# Power_Distribution_-_Spares_6-9.net
KiCad netlist of a schematic drawn in Altium Designer
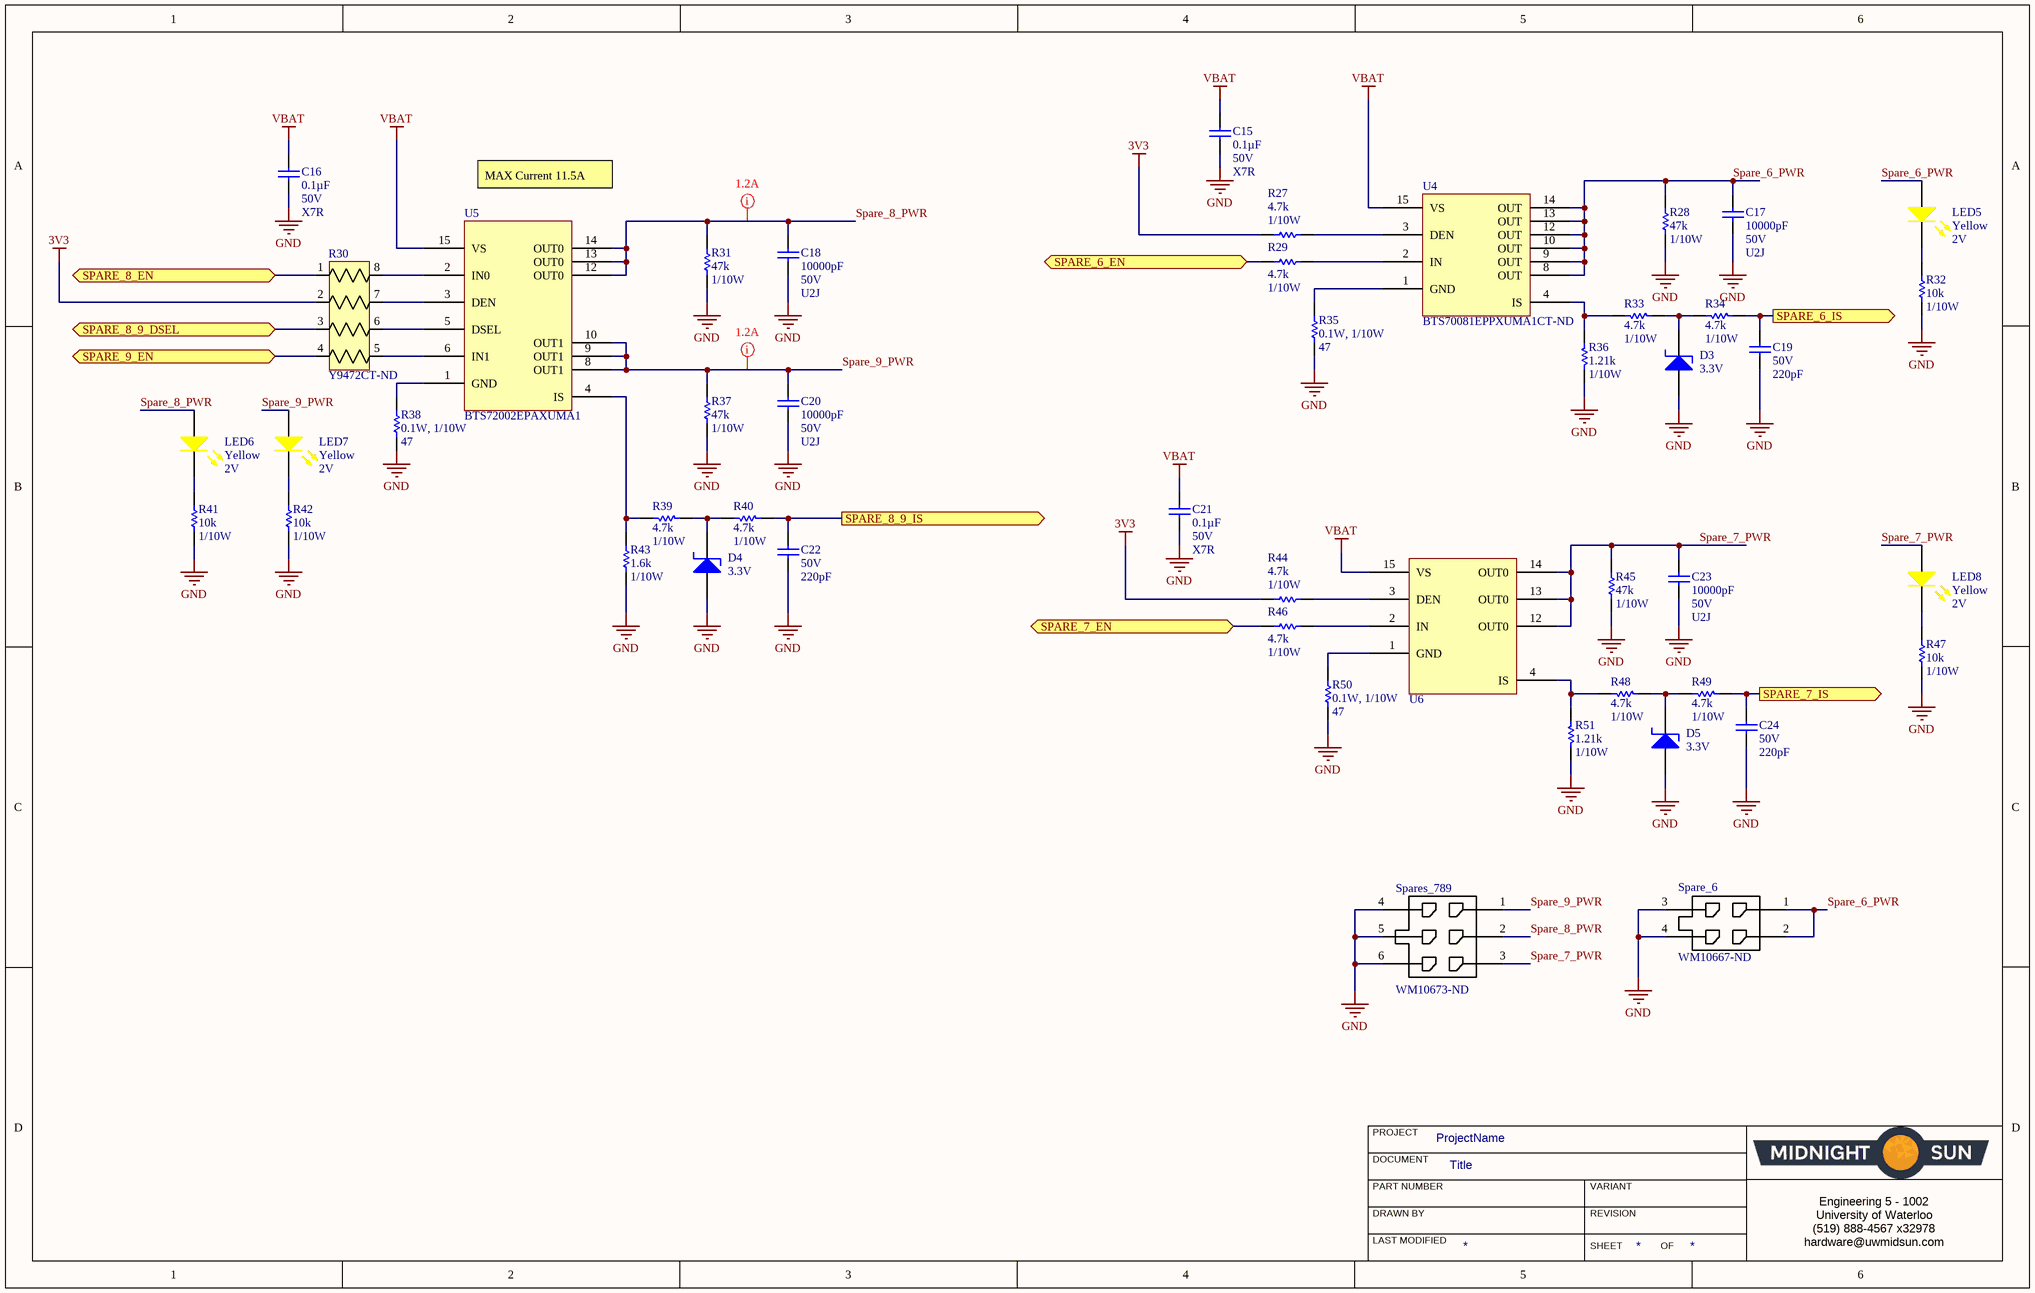
[diagram p0: Power Distribution - Spares 6-9.SchDoc]

(export (version "E")
  (design (tool "Eeschema 10.0.6"))
  (components
    (comp (ref "C15")
      (value "CAP CER 0.1UF 50V 10% X7R 0603")
      (footprint "CAP, 0603")
      (description "0.10µF ±10% 50V Ceramic Capacitor X7R 0603 (1608 Metric)")
      (fields
        (field (name "TOLERANCE") "±10%")
        (field (name "CAPACITANCE") "0.1µF")
        (field (name "VOLTAGE") "50V")
        (field (name "TEMPERATURE COEFFICIENT") "X7R")
      )
      (libsource (lib "Schematic Diagrams") (part "CAP CER 0.1UF 50V 10% X7R 0603"))
    )
    (comp (ref "C16")
      (value "CAP CER 0.1UF 50V 10% X7R 0603")
      (footprint "CAP, 0603")
      (description "0.10µF ±10% 50V Ceramic Capacitor X7R 0603 (1608 Metric)")
      (fields
        (field (name "TOLERANCE") "±10%")
        (field (name "CAPACITANCE") "0.1µF")
        (field (name "VOLTAGE") "50V")
        (field (name "TEMPERATURE COEFFICIENT") "X7R")
      )
      (libsource (lib "Schematic Diagrams") (part "CAP CER 0.1UF 50V 10% X7R 0603"))
    )
    (comp (ref "C17")
      (value "CAP CER 10nF 50V 5% X7R 0603")
      (footprint "CAP, 0603")
      (description "10000pF ±5% 50V Ceramic Capacitor U2J 0603 (1608 Metric)")
      (fields
        (field (name "TOLERANCE") "±5%")
        (field (name "CAPACITANCE") "10000pF")
        (field (name "VOLTAGE") "50V")
        (field (name "TEMPERATURE COEFFICIENT") "U2J")
      )
      (libsource (lib "Schematic Diagrams") (part "CAP CER 10nF 50V 5% X7R 0603"))
    )
    (comp (ref "C18")
      (value "CAP CER 10nF 50V 5% X7R 0603")
      (footprint "CAP, 0603")
      (description "10000pF ±5% 50V Ceramic Capacitor U2J 0603 (1608 Metric)")
      (fields
        (field (name "TOLERANCE") "±5%")
        (field (name "CAPACITANCE") "10000pF")
        (field (name "VOLTAGE") "50V")
        (field (name "TEMPERATURE COEFFICIENT") "U2J")
      )
      (libsource (lib "Schematic Diagrams") (part "CAP CER 10nF 50V 5% X7R 0603"))
    )
    (comp (ref "C19")
      (value "CAP CER 220PF 50V C0G/NP0 0603")
      (footprint "CAP, 0603")
      (description "220pF ±5% 50V Ceramic Capacitor C0G, NP0 0603 (1608 Metric)")
      (fields
        (field (name "MANUFACTURER") "KEMET")
        (field (name "TOLERANCE") "5%")
        (field (name "VOLTAGE RATING") "50V")
        (field (name "CAPACITANCE") "220pF")
      )
      (libsource (lib "Schematic Diagrams") (part "CAP CER 220PF 50V C0G/NP0 0603"))
    )
    (comp (ref "C20")
      (value "CAP CER 10nF 50V 5% X7R 0603")
      (footprint "CAP, 0603")
      (description "10000pF ±5% 50V Ceramic Capacitor U2J 0603 (1608 Metric)")
      (fields
        (field (name "TOLERANCE") "±5%")
        (field (name "CAPACITANCE") "10000pF")
        (field (name "VOLTAGE") "50V")
        (field (name "TEMPERATURE COEFFICIENT") "U2J")
      )
      (libsource (lib "Schematic Diagrams") (part "CAP CER 10nF 50V 5% X7R 0603"))
    )
    (comp (ref "C21")
      (value "CAP CER 0.1UF 50V 10% X7R 0603")
      (footprint "CAP, 0603")
      (description "0.10µF ±10% 50V Ceramic Capacitor X7R 0603 (1608 Metric)")
      (fields
        (field (name "TOLERANCE") "±10%")
        (field (name "CAPACITANCE") "0.1µF")
        (field (name "VOLTAGE") "50V")
        (field (name "TEMPERATURE COEFFICIENT") "X7R")
      )
      (libsource (lib "Schematic Diagrams") (part "CAP CER 0.1UF 50V 10% X7R 0603"))
    )
    (comp (ref "C22")
      (value "CAP CER 220PF 50V C0G/NP0 0603")
      (footprint "CAP, 0603")
      (description "220pF ±5% 50V Ceramic Capacitor C0G, NP0 0603 (1608 Metric)")
      (fields
        (field (name "MANUFACTURER") "KEMET")
        (field (name "TOLERANCE") "5%")
        (field (name "VOLTAGE RATING") "50V")
        (field (name "CAPACITANCE") "220pF")
      )
      (libsource (lib "Schematic Diagrams") (part "CAP CER 220PF 50V C0G/NP0 0603"))
    )
    (comp (ref "C23")
      (value "CAP CER 10nF 50V 5% X7R 0603")
      (footprint "CAP, 0603")
      (description "10000pF ±5% 50V Ceramic Capacitor U2J 0603 (1608 Metric)")
      (fields
        (field (name "TOLERANCE") "±5%")
        (field (name "CAPACITANCE") "10000pF")
        (field (name "VOLTAGE") "50V")
        (field (name "TEMPERATURE COEFFICIENT") "U2J")
      )
      (libsource (lib "Schematic Diagrams") (part "CAP CER 10nF 50V 5% X7R 0603"))
    )
    (comp (ref "C24")
      (value "CAP CER 220PF 50V C0G/NP0 0603")
      (footprint "CAP, 0603")
      (description "220pF ±5% 50V Ceramic Capacitor C0G, NP0 0603 (1608 Metric)")
      (fields
        (field (name "MANUFACTURER") "KEMET")
        (field (name "TOLERANCE") "5%")
        (field (name "VOLTAGE RATING") "50V")
        (field (name "CAPACITANCE") "220pF")
      )
      (libsource (lib "Schematic Diagrams") (part "CAP CER 220PF 50V C0G/NP0 0603"))
    )
    (comp (ref "D3")
      (value "DIODE ZENER 3.3V 200MW SOD323")
      (footprint "sod-323")
      (description "Zener Diode 3.3V 200mW ±5% Surface Mount SOD-323")
      (fields (field (name "VOLTAGE") "3.3V"))
      (libsource (lib "Schematic Diagrams") (part "DIODE ZENER 3.3V 200MW SOD323"))
    )
    (comp (ref "D4")
      (value "DIODE ZENER 3.3V 200MW SOD323")
      (footprint "sod-323")
      (description "Zener Diode 3.3V 200mW ±5% Surface Mount SOD-323")
      (fields (field (name "VOLTAGE") "3.3V"))
      (libsource (lib "Schematic Diagrams") (part "DIODE ZENER 3.3V 200MW SOD323"))
    )
    (comp (ref "D5")
      (value "DIODE ZENER 3.3V 200MW SOD323")
      (footprint "sod-323")
      (description "Zener Diode 3.3V 200mW ±5% Surface Mount SOD-323")
      (fields (field (name "VOLTAGE") "3.3V"))
      (libsource (lib "Schematic Diagrams") (part "DIODE ZENER 3.3V 200MW SOD323"))
    )
    (comp (ref "LED5")
      (value "LED YELLOW CLEAR 2.1V 0603")
      (footprint "LED_0603")
      (description "Yellow 590nm LED Indication - Discrete 2V 0603 (1608 Metric)")
      (fields
        (field (name "MANUFACTURER") "Wurth Electronics Inc.")
        (field (name "MANUFACTURER PART NUMBER") "150060YS75000")
        (field (name "COLOR") "Yellow")
        (field (name "VOLTAGE - FORWARD (VF) (TYP)") "2V")
      )
      (libsource (lib "Schematic Diagrams") (part "LED YELLOW CLEAR 2.1V 0603"))
    )
    (comp (ref "LED6")
      (value "LED YELLOW CLEAR 2.1V 0603")
      (footprint "LED_0603")
      (description "Yellow 590nm LED Indication - Discrete 2V 0603 (1608 Metric)")
      (fields
        (field (name "MANUFACTURER") "Wurth Electronics Inc.")
        (field (name "MANUFACTURER PART NUMBER") "150060YS75000")
        (field (name "COLOR") "Yellow")
        (field (name "VOLTAGE - FORWARD (VF) (TYP)") "2V")
      )
      (libsource (lib "Schematic Diagrams") (part "LED YELLOW CLEAR 2.1V 0603"))
    )
    (comp (ref "LED7")
      (value "LED YELLOW CLEAR 2.1V 0603")
      (footprint "LED_0603")
      (description "Yellow 590nm LED Indication - Discrete 2V 0603 (1608 Metric)")
      (fields
        (field (name "MANUFACTURER") "Wurth Electronics Inc.")
        (field (name "MANUFACTURER PART NUMBER") "150060YS75000")
        (field (name "COLOR") "Yellow")
        (field (name "VOLTAGE - FORWARD (VF) (TYP)") "2V")
      )
      (libsource (lib "Schematic Diagrams") (part "LED YELLOW CLEAR 2.1V 0603"))
    )
    (comp (ref "LED8")
      (value "LED YELLOW CLEAR 2.1V 0603")
      (footprint "LED_0603")
      (description "Yellow 590nm LED Indication - Discrete 2V 0603 (1608 Metric)")
      (fields
        (field (name "MANUFACTURER") "Wurth Electronics Inc.")
        (field (name "MANUFACTURER PART NUMBER") "150060YS75000")
        (field (name "COLOR") "Yellow")
        (field (name "VOLTAGE - FORWARD (VF) (TYP)") "2V")
      )
      (libsource (lib "Schematic Diagrams") (part "LED YELLOW CLEAR 2.1V 0603"))
    )
    (comp (ref "R27")
      (value "RES 4.7K OHM 1% 1/10W 0603")
      (footprint "RES, 0603")
      (description "4.7k Ohm ±1% 0.1W, 1/10W Chip Resistor 0603 (1608 Metric) Moisture Resistant Thick Film")
      (fields
        (field (name "TOLERANCE") "±1%")
        (field (name "RESISTANCE (OHMS)") "4.7k")
        (field (name "POWER (WATTS)") "1/10W")
      )
      (libsource (lib "Schematic Diagrams") (part "RES 4.7K OHM 1% 1/10W 0603"))
    )
    (comp (ref "R28")
      (value "RES 47K OHM 1% 1/10W 0603")
      (footprint "RES, 0603")
      (description "47 kOhms ±1% 0.1W, 1/10W Chip Resistor 0603 (1608 Metric) Automotive AEC-Q200 Thick Film")
      (fields
        (field (name "MANUFACTURER") "Panasonic")
        (field (name "MANUFACTURER PART NUMBER") "ERJ3EKF4702V")
        (field (name "RESISTANCE") "47k")
        (field (name "POWER RATING") "1/10W")
      )
      (libsource (lib "Schematic Diagrams") (part "RES 47K OHM 1% 1/10W 0603"))
    )
    (comp (ref "R29")
      (value "RES 4.7K OHM 1% 1/10W 0603")
      (footprint "RES, 0603")
      (description "4.7k Ohm ±1% 0.1W, 1/10W Chip Resistor 0603 (1608 Metric) Moisture Resistant Thick Film")
      (fields
        (field (name "TOLERANCE") "±1%")
        (field (name "RESISTANCE (OHMS)") "4.7k")
        (field (name "POWER (WATTS)") "1/10W")
      )
      (libsource (lib "Schematic Diagrams") (part "RES 4.7K OHM 1% 1/10W 0603"))
    )
    (comp (ref "R30")
      (value "RES ARRAY 4 RES 4.7K OHM 1206")
      (footprint "RES ARRAY 4RES 1206")
      (fields (field (name "TOLERANCE") "±5%") (field (name "SUPPLIER PART NUMBER 1") "Y9472CT-ND"))
      (libsource (lib "Schematic Diagrams") (part "RES ARRAY 4 RES 4.7K OHM 1206"))
    )
    (comp (ref "R31")
      (value "RES 47K OHM 1% 1/10W 0603")
      (footprint "RES, 0603")
      (description "47 kOhms ±1% 0.1W, 1/10W Chip Resistor 0603 (1608 Metric) Automotive AEC-Q200 Thick Film")
      (fields
        (field (name "MANUFACTURER") "Panasonic")
        (field (name "MANUFACTURER PART NUMBER") "ERJ3EKF4702V")
        (field (name "RESISTANCE") "47k")
        (field (name "POWER RATING") "1/10W")
      )
      (libsource (lib "Schematic Diagrams") (part "RES 47K OHM 1% 1/10W 0603"))
    )
    (comp (ref "R32")
      (value "RES 10K OHM 1% 1/10W 0603")
      (footprint "RES, 0603")
      (description "RES SMD 10K OHM 1% 1/10W 0603")
      (fields
        (field (name "TOLERANCE") "±1%")
        (field (name "RESISTANCE") "10k")
        (field (name "POWER") "1/10W")
      )
      (libsource (lib "Schematic Diagrams") (part "RES 10K OHM 1% 1/10W 0603"))
    )
    (comp (ref "R33")
      (value "RES 4.7K OHM 1% 1/10W 0603")
      (footprint "RES, 0603")
      (description "4.7k Ohm ±1% 0.1W, 1/10W Chip Resistor 0603 (1608 Metric) Moisture Resistant Thick Film")
      (fields
        (field (name "TOLERANCE") "±1%")
        (field (name "RESISTANCE (OHMS)") "4.7k")
        (field (name "POWER (WATTS)") "1/10W")
      )
      (libsource (lib "Schematic Diagrams") (part "RES 4.7K OHM 1% 1/10W 0603"))
    )
    (comp (ref "R34")
      (value "RES 4.7K OHM 1% 1/10W 0603")
      (footprint "RES, 0603")
      (description "4.7k Ohm ±1% 0.1W, 1/10W Chip Resistor 0603 (1608 Metric) Moisture Resistant Thick Film")
      (fields
        (field (name "TOLERANCE") "±1%")
        (field (name "RESISTANCE (OHMS)") "4.7k")
        (field (name "POWER (WATTS)") "1/10W")
      )
      (libsource (lib "Schematic Diagrams") (part "RES 4.7K OHM 1% 1/10W 0603"))
    )
    (comp (ref "R35")
      (value "RES SMD 47 OHM 1% 1/10W 0603")
      (footprint "RES, 0603")
      (fields
        (field (name "TOLERANCE") "±1%")
        (field (name "POWER (WATTS)") "0.1W, 1/10W")
        (field (name "VALUES") "47")
      )
      (libsource (lib "Schematic Diagrams") (part "RES SMD 47 OHM 1% 1/10W 0603"))
    )
    (comp (ref "R36")
      (value "RES 1.21K OHM 1% 1/10W 0603")
      (footprint "RES, 0603")
      (description "1.21k Ohm ±1% 0.1W, 1/10W Chip Resistor 0603 (1608 Metric) Moisture Resistant Thick Film")
      (fields
        (field (name "TOLERANCE") "±1%")
        (field (name "RESISTANCE") "1.21k")
        (field (name "POWER") "1/10W")
      )
      (libsource (lib "Schematic Diagrams") (part "RES 1.21K OHM 1% 1/10W 0603"))
    )
    (comp (ref "R37")
      (value "RES 47K OHM 1% 1/10W 0603")
      (footprint "RES, 0603")
      (description "47 kOhms ±1% 0.1W, 1/10W Chip Resistor 0603 (1608 Metric) Automotive AEC-Q200 Thick Film")
      (fields
        (field (name "MANUFACTURER") "Panasonic")
        (field (name "MANUFACTURER PART NUMBER") "ERJ3EKF4702V")
        (field (name "RESISTANCE") "47k")
        (field (name "POWER RATING") "1/10W")
      )
      (libsource (lib "Schematic Diagrams") (part "RES 47K OHM 1% 1/10W 0603"))
    )
    (comp (ref "R38")
      (value "RES SMD 47 OHM 1% 1/10W 0603")
      (footprint "RES, 0603")
      (fields
        (field (name "TOLERANCE") "±1%")
        (field (name "POWER (WATTS)") "0.1W, 1/10W")
        (field (name "VALUES") "47")
      )
      (libsource (lib "Schematic Diagrams") (part "RES SMD 47 OHM 1% 1/10W 0603"))
    )
    (comp (ref "R39")
      (value "RES 4.7K OHM 1% 1/10W 0603")
      (footprint "RES, 0603")
      (description "4.7k Ohm ±1% 0.1W, 1/10W Chip Resistor 0603 (1608 Metric) Moisture Resistant Thick Film")
      (fields
        (field (name "TOLERANCE") "±1%")
        (field (name "RESISTANCE (OHMS)") "4.7k")
        (field (name "POWER (WATTS)") "1/10W")
      )
      (libsource (lib "Schematic Diagrams") (part "RES 4.7K OHM 1% 1/10W 0603"))
    )
    (comp (ref "R40")
      (value "RES 4.7K OHM 1% 1/10W 0603")
      (footprint "RES, 0603")
      (description "4.7k Ohm ±1% 0.1W, 1/10W Chip Resistor 0603 (1608 Metric) Moisture Resistant Thick Film")
      (fields
        (field (name "TOLERANCE") "±1%")
        (field (name "RESISTANCE (OHMS)") "4.7k")
        (field (name "POWER (WATTS)") "1/10W")
      )
      (libsource (lib "Schematic Diagrams") (part "RES 4.7K OHM 1% 1/10W 0603"))
    )
    (comp (ref "R41")
      (value "RES 10K OHM 1% 1/10W 0603")
      (footprint "RES, 0603")
      (description "RES SMD 10K OHM 1% 1/10W 0603")
      (fields
        (field (name "TOLERANCE") "±1%")
        (field (name "RESISTANCE") "10k")
        (field (name "POWER") "1/10W")
      )
      (libsource (lib "Schematic Diagrams") (part "RES 10K OHM 1% 1/10W 0603"))
    )
    (comp (ref "R42")
      (value "RES 10K OHM 1% 1/10W 0603")
      (footprint "RES, 0603")
      (description "RES SMD 10K OHM 1% 1/10W 0603")
      (fields
        (field (name "TOLERANCE") "±1%")
        (field (name "RESISTANCE") "10k")
        (field (name "POWER") "1/10W")
      )
      (libsource (lib "Schematic Diagrams") (part "RES 10K OHM 1% 1/10W 0603"))
    )
    (comp (ref "R43")
      (value "RES 1.6K OHM 1% 1/10W 0603")
      (footprint "RES, 0603")
      (description "1.6 kOhms ±1% 0.1W, 1/10W Chip Resistor 0603 (1608 Metric) Moisture Resistant Thick Film")
      (fields
        (field (name "MANUFACTURER") "Yageo")
        (field (name "MANUFACTURER PART NUMBER") "RC0603FR-071K6L")
        (field (name "RESISTANCE") "1.6k")
        (field (name "POWER RATING") "1/10W")
      )
      (libsource (lib "Schematic Diagrams") (part "RES 1.6K OHM 1% 1/10W 0603"))
    )
    (comp (ref "R44")
      (value "RES 4.7K OHM 1% 1/10W 0603")
      (footprint "RES, 0603")
      (description "4.7k Ohm ±1% 0.1W, 1/10W Chip Resistor 0603 (1608 Metric) Moisture Resistant Thick Film")
      (fields
        (field (name "TOLERANCE") "±1%")
        (field (name "RESISTANCE (OHMS)") "4.7k")
        (field (name "POWER (WATTS)") "1/10W")
      )
      (libsource (lib "Schematic Diagrams") (part "RES 4.7K OHM 1% 1/10W 0603"))
    )
    (comp (ref "R45")
      (value "RES 47K OHM 1% 1/10W 0603")
      (footprint "RES, 0603")
      (description "47 kOhms ±1% 0.1W, 1/10W Chip Resistor 0603 (1608 Metric) Automotive AEC-Q200 Thick Film")
      (fields
        (field (name "MANUFACTURER") "Panasonic")
        (field (name "MANUFACTURER PART NUMBER") "ERJ3EKF4702V")
        (field (name "RESISTANCE") "47k")
        (field (name "POWER RATING") "1/10W")
      )
      (libsource (lib "Schematic Diagrams") (part "RES 47K OHM 1% 1/10W 0603"))
    )
    (comp (ref "R46")
      (value "RES 4.7K OHM 1% 1/10W 0603")
      (footprint "RES, 0603")
      (description "4.7k Ohm ±1% 0.1W, 1/10W Chip Resistor 0603 (1608 Metric) Moisture Resistant Thick Film")
      (fields
        (field (name "TOLERANCE") "±1%")
        (field (name "RESISTANCE (OHMS)") "4.7k")
        (field (name "POWER (WATTS)") "1/10W")
      )
      (libsource (lib "Schematic Diagrams") (part "RES 4.7K OHM 1% 1/10W 0603"))
    )
    (comp (ref "R47")
      (value "RES 10K OHM 1% 1/10W 0603")
      (footprint "RES, 0603")
      (description "RES SMD 10K OHM 1% 1/10W 0603")
      (fields
        (field (name "TOLERANCE") "±1%")
        (field (name "RESISTANCE") "10k")
        (field (name "POWER") "1/10W")
      )
      (libsource (lib "Schematic Diagrams") (part "RES 10K OHM 1% 1/10W 0603"))
    )
    (comp (ref "R48")
      (value "RES 4.7K OHM 1% 1/10W 0603")
      (footprint "RES, 0603")
      (description "4.7k Ohm ±1% 0.1W, 1/10W Chip Resistor 0603 (1608 Metric) Moisture Resistant Thick Film")
      (fields
        (field (name "TOLERANCE") "±1%")
        (field (name "RESISTANCE (OHMS)") "4.7k")
        (field (name "POWER (WATTS)") "1/10W")
      )
      (libsource (lib "Schematic Diagrams") (part "RES 4.7K OHM 1% 1/10W 0603"))
    )
    (comp (ref "R49")
      (value "RES 4.7K OHM 1% 1/10W 0603")
      (footprint "RES, 0603")
      (description "4.7k Ohm ±1% 0.1W, 1/10W Chip Resistor 0603 (1608 Metric) Moisture Resistant Thick Film")
      (fields
        (field (name "TOLERANCE") "±1%")
        (field (name "RESISTANCE (OHMS)") "4.7k")
        (field (name "POWER (WATTS)") "1/10W")
      )
      (libsource (lib "Schematic Diagrams") (part "RES 4.7K OHM 1% 1/10W 0603"))
    )
    (comp (ref "R50")
      (value "RES SMD 47 OHM 1% 1/10W 0603")
      (footprint "RES, 0603")
      (fields
        (field (name "TOLERANCE") "±1%")
        (field (name "POWER (WATTS)") "0.1W, 1/10W")
        (field (name "VALUES") "47")
      )
      (libsource (lib "Schematic Diagrams") (part "RES SMD 47 OHM 1% 1/10W 0603"))
    )
    (comp (ref "R51")
      (value "RES 1.21K OHM 1% 1/10W 0603")
      (footprint "RES, 0603")
      (description "1.21k Ohm ±1% 0.1W, 1/10W Chip Resistor 0603 (1608 Metric) Moisture Resistant Thick Film")
      (fields
        (field (name "TOLERANCE") "±1%")
        (field (name "RESISTANCE") "1.21k")
        (field (name "POWER") "1/10W")
      )
      (libsource (lib "Schematic Diagrams") (part "RES 1.21K OHM 1% 1/10W 0603"))
    )
    (comp (ref "Spares_789")
      (value "CONN 6POS MICRO-FIT 3mm")
      (footprint "CONN, 6POS MICRO-FIT 3MM")
      (description "Connector Header Through Hole 6 position 0.118\" (3.00mm)")
      (fields (field (name "SUPPLIER PART NUMBER 1") "WM10673-ND"))
      (libsource (lib "Schematic Diagrams") (part "CONN 6POS MICRO-FIT 3mm"))
    )
    (comp (ref "Spare_6")
      (value "CONN 4POS MICRO-FIT 3mm")
      (footprint "CONN 4POS MICROFIT (2x2)")
      (fields
        (field (name "MANUFACTURER") "Molex, LLC")
        (field (name "MANUFACTURER PART NUMBER") "430450427")
        (field (name "SUPPLIER PART NUMBER 1") "WM10667-ND")
      )
      (libsource (lib "Schematic Diagrams") (part "CONN 4POS MICRO-FIT 3mm"))
    )
    (comp (ref "U4")
      (value "IC LOAD SWITCH BTS70081EPPXUMA1")
      (footprint "IC LOAD SWITCH PG-TSDSO-14-22")
      (description "Power Switch/Driver 1:1 N-Channel 11A PG-TSDSO-14-22")
      (fields
        (field (name "MANUFACTURER") "Infineon")
        (field (name "MANUFACTURER PART NUMBER") "BTS70081EPPXUMA1CT-ND")
      )
      (libsource (lib "Schematic Diagrams") (part "IC LOAD SWITCH BTS70081EPPXUMA1"))
    )
    (comp (ref "U5")
      (value "IC LOAD SWITCH BTS7200-2EPA PG-TSDSO-14_1")
      (footprint "IC LOAD SWITCH PG-TSDSO-14-22")
      (description "Power Switch/Driver 1:1 N-Channel 1.2A PG-TSDSO-14-22")
      (fields
        (field (name "MANUFACTURER") "Infineon")
        (field (name "MANUFACTURER PART NUMBER") "BTS72002EPAXUMA1")
      )
      (libsource (lib "Schematic Diagrams") (part "IC LOAD SWITCH BTS7200-2EPA PG-TSDSO-14_1"))
    )
    (comp (ref "U6")
      (value "IC LOAD SWITCH BTS70401EPA PG-TSDSO-14-22")
      (footprint "IC LOAD SWITCH PG-TSDSO-14-22")
      (description "Power Switch/Driver 1:1 N-Channel 4.5A PG-TSDSO-14-22")
      (fields
        (field (name "MANUFACTURER") "Infineon")
        (field (name "MANUFACTURER PART NUMBER") "BTS70401EPAXUMA1")
      )
      (libsource (lib "Schematic Diagrams") (part "IC LOAD SWITCH BTS70401EPA PG-TSDSO-14-22"))
    )
  )
  (nets
    (net (code "1") (name "/SPARE_6_EN") (class "Default")
      (node (ref "R29") (pin "1") (pinfunction "1_1") (pintype "passive"))
    )
    (net (code "2") (name "/SPARE_6_IS") (class "Default")
      (node (ref "C19") (pin "1") (pinfunction "1_1") (pintype "passive"))
      (node (ref "R34") (pin "1") (pinfunction "1_1") (pintype "passive"))
    )
    (net (code "3") (name "/SPARE_7_EN") (class "Default")
      (node (ref "R46") (pin "1") (pinfunction "1_1") (pintype "passive"))
    )
    (net (code "4") (name "/SPARE_7_IS") (class "Default")
      (node (ref "C24") (pin "1") (pinfunction "1_1") (pintype "passive"))
      (node (ref "R49") (pin "1") (pinfunction "1_1") (pintype "passive"))
    )
    (net (code "5") (name "/SPARE_8_9_DSEL") (class "Default")
      (node (ref "R30") (pin "3") (pinfunction "3_3") (pintype "passive"))
    )
    (net (code "6") (name "/SPARE_8_9_IS") (class "Default")
      (node (ref "C22") (pin "1") (pinfunction "1_1") (pintype "passive"))
      (node (ref "R40") (pin "1") (pinfunction "1_1") (pintype "passive"))
    )
    (net (code "7") (name "/SPARE_8_EN") (class "Default")
      (node (ref "R30") (pin "1") (pinfunction "1_1") (pintype "passive"))
    )
    (net (code "8") (name "/SPARE_9_EN") (class "Default")
      (node (ref "R30") (pin "4") (pinfunction "4_4") (pintype "passive"))
    )
    (net (code "9") (name "/Spare_6_PWR") (class "Default")
      (node (ref "C17") (pin "1") (pinfunction "1_1") (pintype "passive"))
      (node (ref "LED5") (pin "1") (pinfunction "A_1") (pintype "passive"))
      (node (ref "R28") (pin "1") (pinfunction "1_1") (pintype "passive"))
      (node (ref "Spare_6") (pin "1") (pinfunction "1_1") (pintype "passive"))
      (node (ref "Spare_6") (pin "2") (pinfunction "2_2") (pintype "passive"))
      (node (ref "U4") (pin "10") (pinfunction "OUT_10") (pintype "passive"))
      (node (ref "U4") (pin "12") (pinfunction "OUT_12") (pintype "passive"))
      (node (ref "U4") (pin "13") (pinfunction "OUT_13") (pintype "passive"))
      (node (ref "U4") (pin "14") (pinfunction "OUT_14") (pintype "passive"))
      (node (ref "U4") (pin "8") (pinfunction "OUT_8") (pintype "passive"))
      (node (ref "U4") (pin "9") (pinfunction "OUT_9") (pintype "passive"))
    )
    (net (code "10") (name "/Spare_7_PWR") (class "Default")
      (node (ref "C23") (pin "1") (pinfunction "1_1") (pintype "passive"))
      (node (ref "LED8") (pin "1") (pinfunction "A_1") (pintype "passive"))
      (node (ref "R45") (pin "1") (pinfunction "1_1") (pintype "passive"))
      (node (ref "Spares_789") (pin "3") (pinfunction "3_3") (pintype "passive"))
      (node (ref "U6") (pin "12") (pinfunction "OUT0_12") (pintype "passive"))
      (node (ref "U6") (pin "13") (pinfunction "OUT0_13") (pintype "passive"))
      (node (ref "U6") (pin "14") (pinfunction "OUT0_14") (pintype "passive"))
    )
    (net (code "11") (name "/Spare_8_PWR") (class "Default")
      (node (ref "C18") (pin "1") (pinfunction "1_1") (pintype "passive"))
      (node (ref "LED6") (pin "1") (pinfunction "A_1") (pintype "passive"))
      (node (ref "R31") (pin "1") (pinfunction "1_1") (pintype "passive"))
      (node (ref "Spares_789") (pin "2") (pinfunction "2_2") (pintype "passive"))
      (node (ref "U5") (pin "12") (pinfunction "OUT0_12") (pintype "passive"))
      (node (ref "U5") (pin "13") (pinfunction "OUT0_13") (pintype "passive"))
      (node (ref "U5") (pin "14") (pinfunction "OUT0_14") (pintype "passive"))
    )
    (net (code "12") (name "/Spare_9_PWR") (class "Default")
      (node (ref "C20") (pin "1") (pinfunction "1_1") (pintype "passive"))
      (node (ref "LED7") (pin "1") (pinfunction "A_1") (pintype "passive"))
      (node (ref "R37") (pin "1") (pinfunction "1_1") (pintype "passive"))
      (node (ref "Spares_789") (pin "1") (pinfunction "1_1") (pintype "passive"))
      (node (ref "U5") (pin "10") (pinfunction "OUT1_10") (pintype "passive"))
      (node (ref "U5") (pin "8") (pinfunction "OUT1_8") (pintype "passive"))
      (node (ref "U5") (pin "9") (pinfunction "OUT1_9") (pintype "passive"))
    )
    (net (code "13") (name "3V3") (class "Default")
      (node (ref "R27") (pin "1") (pinfunction "1_1") (pintype "passive"))
      (node (ref "R30") (pin "2") (pinfunction "2_2") (pintype "passive"))
      (node (ref "R44") (pin "1") (pinfunction "1_1") (pintype "passive"))
    )
    (net (code "14") (name "GND") (class "Default")
      (node (ref "C15") (pin "2") (pinfunction "2_2") (pintype "passive"))
      (node (ref "C16") (pin "2") (pinfunction "2_2") (pintype "passive"))
      (node (ref "C17") (pin "2") (pinfunction "2_2") (pintype "passive"))
      (node (ref "C18") (pin "2") (pinfunction "2_2") (pintype "passive"))
      (node (ref "C19") (pin "2") (pinfunction "2_2") (pintype "passive"))
      (node (ref "C20") (pin "2") (pinfunction "2_2") (pintype "passive"))
      (node (ref "C21") (pin "2") (pinfunction "2_2") (pintype "passive"))
      (node (ref "C22") (pin "2") (pinfunction "2_2") (pintype "passive"))
      (node (ref "C23") (pin "2") (pinfunction "2_2") (pintype "passive"))
      (node (ref "C24") (pin "2") (pinfunction "2_2") (pintype "passive"))
      (node (ref "D3") (pin "1") (pinfunction "A_1") (pintype "passive"))
      (node (ref "D4") (pin "1") (pinfunction "A_1") (pintype "passive"))
      (node (ref "D5") (pin "1") (pinfunction "A_1") (pintype "passive"))
      (node (ref "R28") (pin "2") (pinfunction "2_2") (pintype "passive"))
      (node (ref "R31") (pin "2") (pinfunction "2_2") (pintype "passive"))
      (node (ref "R32") (pin "2") (pinfunction "2_2") (pintype "passive"))
      (node (ref "R35") (pin "2") (pinfunction "2_2") (pintype "passive"))
      (node (ref "R36") (pin "2") (pinfunction "2_2") (pintype "passive"))
      (node (ref "R37") (pin "2") (pinfunction "2_2") (pintype "passive"))
      (node (ref "R38") (pin "2") (pinfunction "2_2") (pintype "passive"))
      (node (ref "R41") (pin "2") (pinfunction "2_2") (pintype "passive"))
      (node (ref "R42") (pin "2") (pinfunction "2_2") (pintype "passive"))
      (node (ref "R43") (pin "2") (pinfunction "2_2") (pintype "passive"))
      (node (ref "R45") (pin "2") (pinfunction "2_2") (pintype "passive"))
      (node (ref "R47") (pin "2") (pinfunction "2_2") (pintype "passive"))
      (node (ref "R50") (pin "2") (pinfunction "2_2") (pintype "passive"))
      (node (ref "R51") (pin "2") (pinfunction "2_2") (pintype "passive"))
      (node (ref "Spare_6") (pin "3") (pinfunction "3_3") (pintype "passive"))
      (node (ref "Spare_6") (pin "4") (pinfunction "4_4") (pintype "passive"))
      (node (ref "Spares_789") (pin "4") (pinfunction "4_4") (pintype "passive"))
      (node (ref "Spares_789") (pin "5") (pinfunction "5_5") (pintype "passive"))
      (node (ref "Spares_789") (pin "6") (pinfunction "6_6") (pintype "passive"))
    )
    (net (code "15") (name "Net-(D3-K)") (class "Default")
      (node (ref "D3") (pin "2") (pinfunction "K_2") (pintype "passive"))
      (node (ref "R33") (pin "1") (pinfunction "1_1") (pintype "passive"))
      (node (ref "R34") (pin "2") (pinfunction "2_2") (pintype "passive"))
    )
    (net (code "16") (name "Net-(D4-K)") (class "Default")
      (node (ref "D4") (pin "2") (pinfunction "K_2") (pintype "passive"))
      (node (ref "R39") (pin "1") (pinfunction "1_1") (pintype "passive"))
      (node (ref "R40") (pin "2") (pinfunction "2_2") (pintype "passive"))
    )
    (net (code "17") (name "Net-(D5-K)") (class "Default")
      (node (ref "D5") (pin "2") (pinfunction "K_2") (pintype "passive"))
      (node (ref "R48") (pin "1") (pinfunction "1_1") (pintype "passive"))
      (node (ref "R49") (pin "2") (pinfunction "2_2") (pintype "passive"))
    )
    (net (code "18") (name "Net-(LED5-K)") (class "Default")
      (node (ref "LED5") (pin "2") (pinfunction "K_2") (pintype "passive"))
      (node (ref "R32") (pin "1") (pinfunction "1_1") (pintype "passive"))
    )
    (net (code "19") (name "Net-(LED6-K)") (class "Default")
      (node (ref "LED6") (pin "2") (pinfunction "K_2") (pintype "passive"))
      (node (ref "R41") (pin "1") (pinfunction "1_1") (pintype "passive"))
    )
    (net (code "20") (name "Net-(LED7-K)") (class "Default")
      (node (ref "LED7") (pin "2") (pinfunction "K_2") (pintype "passive"))
      (node (ref "R42") (pin "1") (pinfunction "1_1") (pintype "passive"))
    )
    (net (code "21") (name "Net-(LED8-K)") (class "Default")
      (node (ref "LED8") (pin "2") (pinfunction "K_2") (pintype "passive"))
      (node (ref "R47") (pin "1") (pinfunction "1_1") (pintype "passive"))
    )
    (net (code "22") (name "Net-(U4-DEN)") (class "Default")
      (node (ref "R27") (pin "2") (pinfunction "2_2") (pintype "passive"))
      (node (ref "U4") (pin "3") (pinfunction "DEN_3") (pintype "passive"))
    )
    (net (code "23") (name "Net-(U4-GND)") (class "Default")
      (node (ref "R35") (pin "1") (pinfunction "1_1") (pintype "passive"))
      (node (ref "U4") (pin "1") (pinfunction "GND_1") (pintype "passive"))
    )
    (net (code "24") (name "Net-(U4-IN)") (class "Default")
      (node (ref "R29") (pin "2") (pinfunction "2_2") (pintype "passive"))
      (node (ref "U4") (pin "2") (pinfunction "IN_2") (pintype "passive"))
    )
    (net (code "25") (name "Net-(U4-IS)") (class "Default")
      (node (ref "R33") (pin "2") (pinfunction "2_2") (pintype "passive"))
      (node (ref "R36") (pin "1") (pinfunction "1_1") (pintype "passive"))
      (node (ref "U4") (pin "4") (pinfunction "IS_4") (pintype "passive"))
    )
    (net (code "26") (name "Net-(U5-DEN)") (class "Default")
      (node (ref "R30") (pin "7") (pinfunction "7_7") (pintype "passive"))
      (node (ref "U5") (pin "3") (pinfunction "DEN_3") (pintype "passive"))
    )
    (net (code "27") (name "Net-(U5-DSEL)") (class "Default")
      (node (ref "R30") (pin "6") (pinfunction "6_6") (pintype "passive"))
      (node (ref "U5") (pin "5") (pinfunction "DSEL_5") (pintype "passive"))
    )
    (net (code "28") (name "Net-(U5-GND)") (class "Default")
      (node (ref "R38") (pin "1") (pinfunction "1_1") (pintype "passive"))
      (node (ref "U5") (pin "1") (pinfunction "GND_1") (pintype "passive"))
    )
    (net (code "29") (name "Net-(U5-IN0)") (class "Default")
      (node (ref "R30") (pin "8") (pinfunction "8_8") (pintype "passive"))
      (node (ref "U5") (pin "2") (pinfunction "IN0_2") (pintype "passive"))
    )
    (net (code "30") (name "Net-(U5-IN1)") (class "Default")
      (node (ref "R30") (pin "5") (pinfunction "5_5") (pintype "passive"))
      (node (ref "U5") (pin "6") (pinfunction "IN1_6") (pintype "passive"))
    )
    (net (code "31") (name "Net-(U5-IS)") (class "Default")
      (node (ref "R39") (pin "2") (pinfunction "2_2") (pintype "passive"))
      (node (ref "R43") (pin "1") (pinfunction "1_1") (pintype "passive"))
      (node (ref "U5") (pin "4") (pinfunction "IS_4") (pintype "passive"))
    )
    (net (code "32") (name "Net-(U6-DEN)") (class "Default")
      (node (ref "R44") (pin "2") (pinfunction "2_2") (pintype "passive"))
      (node (ref "U6") (pin "3") (pinfunction "DEN_3") (pintype "passive"))
    )
    (net (code "33") (name "Net-(U6-GND)") (class "Default")
      (node (ref "R50") (pin "1") (pinfunction "1_1") (pintype "passive"))
      (node (ref "U6") (pin "1") (pinfunction "GND_1") (pintype "passive"))
    )
    (net (code "34") (name "Net-(U6-IN)") (class "Default")
      (node (ref "R46") (pin "2") (pinfunction "2_2") (pintype "passive"))
      (node (ref "U6") (pin "2") (pinfunction "IN_2") (pintype "passive"))
    )
    (net (code "35") (name "Net-(U6-IS)") (class "Default")
      (node (ref "R48") (pin "2") (pinfunction "2_2") (pintype "passive"))
      (node (ref "R51") (pin "1") (pinfunction "1_1") (pintype "passive"))
      (node (ref "U6") (pin "4") (pinfunction "IS_4") (pintype "passive"))
    )
    (net (code "36") (name "VBAT") (class "Default")
      (node (ref "C15") (pin "1") (pinfunction "1_1") (pintype "passive"))
      (node (ref "C16") (pin "1") (pinfunction "1_1") (pintype "passive"))
      (node (ref "C21") (pin "1") (pinfunction "1_1") (pintype "passive"))
      (node (ref "U4") (pin "15") (pinfunction "VS_15") (pintype "passive"))
      (node (ref "U5") (pin "15") (pinfunction "VS_15") (pintype "passive"))
      (node (ref "U6") (pin "15") (pinfunction "VS_15") (pintype "passive"))
    )
  )
)
